# YOTSUBA_GNSS-receiver_MAX_ver_1_5b.net
KiCad netlist of a schematic drawn in EAGLE
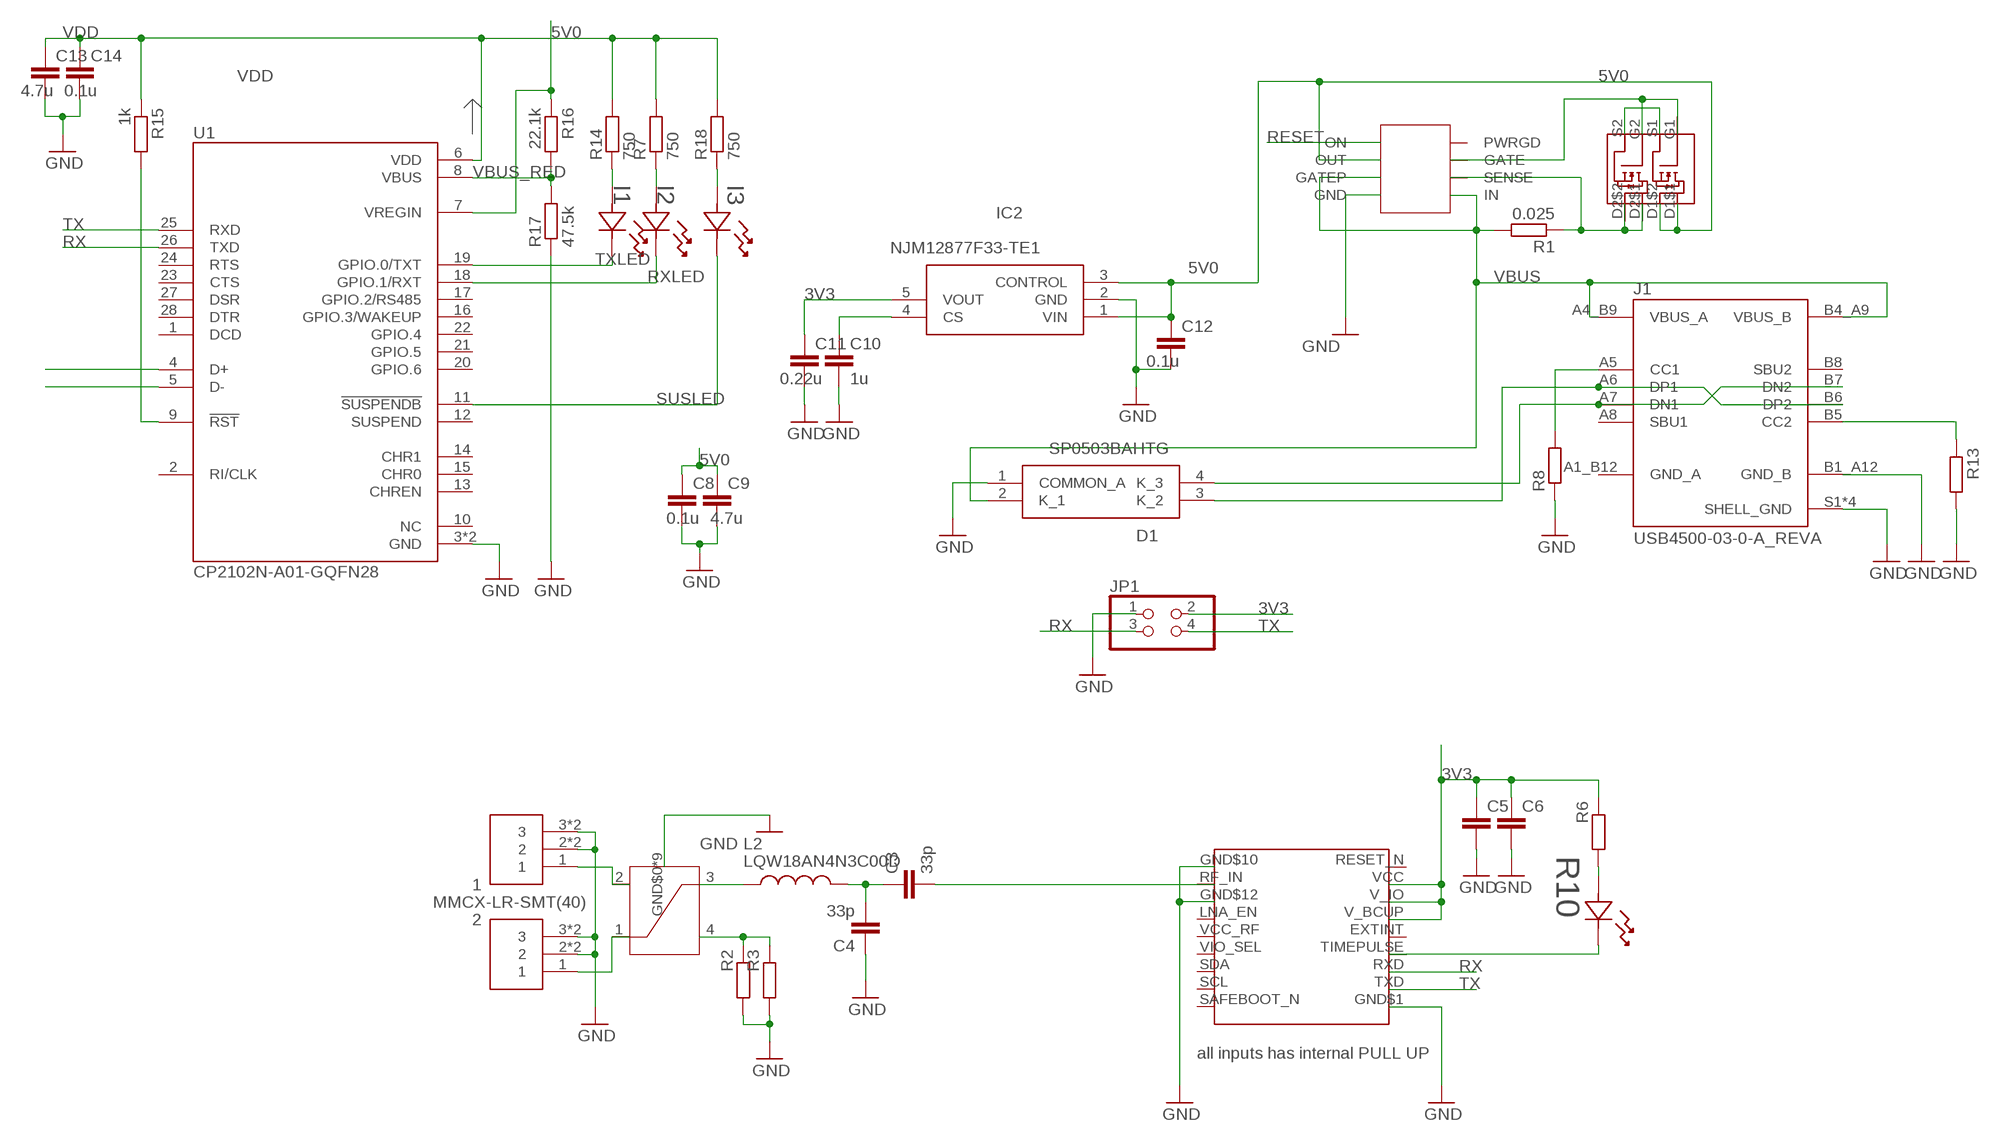
[diagram p0: schematic, sheet 1]

(export (version "E")
  (design (tool "Eeschema 10.0.6"))
  (components
    (comp (ref "1")
      (value "MMCX-LR-SMT(40)")
      (footprint "eagle-import:MMCX-LR-SMT(40)")
      (libsource (lib "eagle-import") (part "MMCX-LR-SMT(40)"))
    )
    (comp (ref "2")
      (value "MMCX-LR-SMT(40)")
      (footprint "eagle-import:MMCX-LR-SMT(40)")
      (libsource (lib "eagle-import") (part "MMCX-LR-SMT(40)"))
    )
    (comp (ref "C3")
      (value "33p")
      (footprint "eagle-import:C1608")
      (libsource (lib "eagle-import") (part "C-EUC1608"))
    )
    (comp (ref "C4")
      (value "33p")
      (footprint "eagle-import:C1608")
      (libsource (lib "eagle-import") (part "C-EUC1608"))
    )
    (comp (ref "C5")
      (value "C-EUC1608")
      (footprint "eagle-import:C1608")
      (libsource (lib "eagle-import") (part "C-EUC1608"))
    )
    (comp (ref "C6")
      (value "C-EUC1608")
      (footprint "eagle-import:C1608")
      (libsource (lib "eagle-import") (part "C-EUC1608"))
    )
    (comp (ref "C8")
      (value "0.1u")
      (footprint "eagle-import:C1608")
      (libsource (lib "eagle-import") (part "C-EUC1608"))
    )
    (comp (ref "C9")
      (value "4.7u")
      (footprint "eagle-import:C1608")
      (libsource (lib "eagle-import") (part "C-EUC1608"))
    )
    (comp (ref "C10")
      (value "1u")
      (footprint "eagle-import:C1608")
      (libsource (lib "eagle-import") (part "C-EUC1608"))
    )
    (comp (ref "C11")
      (value "0.22u")
      (footprint "eagle-import:C1608")
      (libsource (lib "eagle-import") (part "C-EUC1608"))
    )
    (comp (ref "C12")
      (value "0.1u")
      (footprint "eagle-import:C1608")
      (libsource (lib "eagle-import") (part "C-EUC1608"))
    )
    (comp (ref "C13")
      (value "4.7u")
      (footprint "eagle-import:C1608")
      (libsource (lib "eagle-import") (part "C-EUC1608"))
    )
    (comp (ref "C14")
      (value "0.1u")
      (footprint "eagle-import:C1608")
      (libsource (lib "eagle-import") (part "C-EUC1608"))
    )
    (comp (ref "D1")
      (value "SP0503BAHTG")
      (footprint "eagle-import:SP0503BAHTG")
      (fields (field (name "MOUSER_PART_NUMBER") "576-SP0503BAHTG"))
      (libsource (lib "eagle-import") (part "SP0503BAHTG"))
    )
    (comp (ref "I1")
      (value "SML-E12P8WT86")
      (footprint "eagle-import:LED_SMLD12_ROM")
      (fields (field (name "COPYRIGHT") "Copyright (C) 2023 Ultra Librarian. All rights reserved."))
      (libsource (lib "eagle-import") (part "SML-E12P8WT86"))
    )
    (comp (ref "I2")
      (value "SML-E12P8WT86")
      (footprint "eagle-import:LED_SMLD12_ROM")
      (fields (field (name "COPYRIGHT") "Copyright (C) 2023 Ultra Librarian. All rights reserved."))
      (libsource (lib "eagle-import") (part "SML-E12P8WT86"))
    )
    (comp (ref "I3")
      (value "SML-E12P8WT86")
      (footprint "eagle-import:LED_SMLD12_ROM")
      (fields (field (name "COPYRIGHT") "Copyright (C) 2023 Ultra Librarian. All rights reserved."))
      (libsource (lib "eagle-import") (part "SML-E12P8WT86"))
    )
    (comp (ref "IC2")
      (value "NJM12877F33-TE1")
      (footprint "eagle-import:SOT95P280X120-5N")
      (fields (field (name "MOUSER_PART_NUMBER") "513-NJM12877F33-TE1"))
      (libsource (lib "eagle-import") (part "NJM12877F33-TE1"))
    )
    (comp (ref "J1")
      (value "USB4500-03-0-A_REVA")
      (footprint "eagle-import:GCT_USB4500-03-0-A_REVA")
      (fields
        (field (name "DIGI-KEY_PART_NUMBER") "2073-USB4500-03-0-ATR-ND")
        (field (name "MF") "Global Connector Technology")
        (field (name "MP") "USB4500-03-0-A")
      )
      (libsource (lib "eagle-import") (part "USB4500-03-0-A_REVA"))
    )
    (comp (ref "JP1")
      (value "PINHD-2X2")
      (footprint "eagle-import:2X02")
      (libsource (lib "eagle-import") (part "PINHD-2X2"))
    )
    (comp (ref "L2")
      (value "LQW18AN4N3C00D")
      (footprint "eagle-import:INDC1608X100N")
      (fields (field (name "DIGIKEY_PART_NUMBER") "490-6896-2-ND") (field (name "MF") "Murata"))
      (libsource (lib "eagle-import") (part "LQW18AN4N3C00D"))
    )
    (comp (ref "R1")
      (value "0.025")
      (footprint "eagle-import:R0603")
      (libsource (lib "eagle-import") (part "R-EU_R0603"))
    )
    (comp (ref "R2")
      (value "R-EU_R0603")
      (footprint "eagle-import:R0603")
      (libsource (lib "eagle-import") (part "R-EU_R0603"))
    )
    (comp (ref "R3")
      (value "R-EU_R0603")
      (footprint "eagle-import:R0603")
      (libsource (lib "eagle-import") (part "R-EU_R0603"))
    )
    (comp (ref "R6")
      (value "R-EU_R0603")
      (footprint "eagle-import:R0603")
      (libsource (lib "eagle-import") (part "R-EU_R0603"))
    )
    (comp (ref "R7")
      (value "750")
      (footprint "eagle-import:R0603")
      (libsource (lib "eagle-import") (part "R-EU_R0603"))
    )
    (comp (ref "R8")
      (value "R-EU_R0603")
      (footprint "eagle-import:R0603")
      (libsource (lib "eagle-import") (part "R-EU_R0603"))
    )
    (comp (ref "R10")
      (value "SML-E12P8WT86")
      (footprint "eagle-import:LED_SMLD12_ROM")
      (fields (field (name "COPYRIGHT") "Copyright (C) 2023 Ultra Librarian. All rights reserved."))
      (libsource (lib "eagle-import") (part "SML-E12P8WT86"))
    )
    (comp (ref "R13")
      (value "R-EU_R0603")
      (footprint "eagle-import:R0603")
      (libsource (lib "eagle-import") (part "R-EU_R0603"))
    )
    (comp (ref "R14")
      (value "750")
      (footprint "eagle-import:R0603")
      (libsource (lib "eagle-import") (part "R-EU_R0603"))
    )
    (comp (ref "R15")
      (value "1k")
      (footprint "eagle-import:R0603")
      (libsource (lib "eagle-import") (part "R-EU_R0603"))
    )
    (comp (ref "R16")
      (value "22.1k")
      (footprint "eagle-import:R0603")
      (libsource (lib "eagle-import") (part "R-EU_R0603"))
    )
    (comp (ref "R17")
      (value "47.5k")
      (footprint "eagle-import:R0603")
      (libsource (lib "eagle-import") (part "R-EU_R0603"))
    )
    (comp (ref "R18")
      (value "750")
      (footprint "eagle-import:R0603")
      (libsource (lib "eagle-import") (part "R-EU_R0603"))
    )
    (comp (ref "U$1")
      (value "MAX_M10S")
      (footprint "eagle-import:MAX-M10S")
      (libsource (lib "eagle-import") (part "MAX_M10S"))
    )
    (comp (ref "U$3")
      (value "HC125.A")
      (footprint "eagle-import:HC125.A")
      (libsource (lib "eagle-import") (part "HC125.A"))
    )
    (comp (ref "U$7")
      (value "DMG6898LSD")
      (footprint "eagle-import:SOIC127P600X150-8N")
      (libsource (lib "eagle-import") (part "DMG6898LSD"))
    )
    (comp (ref "U$8")
      (value "LTC4361")
      (footprint "eagle-import:SOP65P280X100-8N")
      (libsource (lib "eagle-import") (part "LTC4361"))
    )
    (comp (ref "U1")
      (value "CP2102N-A01-GQFN28")
      (footprint "eagle-import:QFN50P500X500X80-29N")
      (fields (field (name "MF") "Silicon Labs"))
      (libsource (lib "eagle-import") (part "CP2102N-A01-GQFN28"))
    )
  )
  (nets
    (net (code "1") (name "/3V3") (class "Default")
      (node (ref "C11") (pin "1") (pinfunction "1_1") (pintype "passive"))
      (node (ref "C5") (pin "1") (pinfunction "1_1") (pintype "passive"))
      (node (ref "C6") (pin "1") (pinfunction "1_1") (pintype "passive"))
      (node (ref "IC2") (pin "5") (pinfunction "VOUT_5") (pintype "bidirectional"))
      (node (ref "JP1") (pin "2") (pinfunction "2_2") (pintype "passive"))
      (node (ref "R6") (pin "2") (pinfunction "2_2") (pintype "passive"))
      (node (ref "U$1") (pin "VCC") (pinfunction "VCC_VCC") (pintype "bidirectional"))
      (node (ref "U$1") (pin "V_BCUP") (pinfunction "V_BCKP_V_BCUP") (pintype "bidirectional"))
      (node (ref "U$1") (pin "V_IO") (pinfunction "V_IO_V_IO") (pintype "bidirectional"))
    )
    (net (code "2") (name "/5V0") (class "Default")
      (node (ref "C12") (pin "1") (pinfunction "1_1") (pintype "passive"))
      (node (ref "C8") (pin "1") (pinfunction "1_1") (pintype "passive"))
      (node (ref "C9") (pin "1") (pinfunction "1_1") (pintype "passive"))
      (node (ref "IC2") (pin "1") (pinfunction "VIN_1") (pintype "bidirectional"))
      (node (ref "IC2") (pin "3") (pinfunction "CONTROL_3") (pintype "bidirectional"))
      (node (ref "R16") (pin "1") (pinfunction "1_1") (pintype "passive"))
      (node (ref "U$7") (pin "D1$1") (pinfunction "D1$1_D1$1") (pintype "bidirectional"))
      (node (ref "U$7") (pin "D1$2") (pinfunction "D1$2_D1$2") (pintype "bidirectional"))
      (node (ref "U$8") (pin "OUT") (pinfunction "OUT_OUT") (pintype "bidirectional"))
      (node (ref "U1") (pin "7") (pinfunction "VREGIN_7") (pintype "power_in"))
    )
    (net (code "3") (name "/D+") (class "Default")
      (node (ref "D1") (pin "3") (pinfunction "K_2_3") (pintype "bidirectional"))
      (node (ref "J1") (pin "A6") (pinfunction "DP1_A6") (pintype "bidirectional"))
      (node (ref "J1") (pin "B6") (pinfunction "DP2_B6") (pintype "bidirectional"))
      (node (ref "U1") (pin "4") (pinfunction "D+_4") (pintype "bidirectional"))
    )
    (net (code "4") (name "/D-") (class "Default")
      (node (ref "D1") (pin "4") (pinfunction "K_3_4") (pintype "bidirectional"))
      (node (ref "J1") (pin "A7") (pinfunction "DN1_A7") (pintype "bidirectional"))
      (node (ref "J1") (pin "B7") (pinfunction "DN2_B7") (pintype "bidirectional"))
      (node (ref "U1") (pin "5") (pinfunction "D-_5") (pintype "bidirectional"))
    )
    (net (code "5") (name "/GND_A") (class "Default")
      (node (ref "J1") (pin "A1_B12") (pinfunction "GND_A_A1_B12") (pintype "power_in"))
    )
    (net (code "6") (name "/RESET") (class "Default")
      (node (ref "U$8") (pin "ON") (pinfunction "ON_ON") (pintype "bidirectional"))
    )
    (net (code "7") (name "/RX") (class "Default")
      (node (ref "JP1") (pin "3") (pinfunction "3_3") (pintype "passive"))
      (node (ref "U$1") (pin "RXD") (pinfunction "RXD_RXD") (pintype "bidirectional"))
      (node (ref "U1") (pin "26") (pinfunction "TXD_26") (pintype "output"))
    )
    (net (code "8") (name "/RXLED") (class "Default")
      (node (ref "I2") (pin "1") (pinfunction "1_1") (pintype "passive"))
      (node (ref "U1") (pin "18") (pinfunction "GPIO.1/RXT_18") (pintype "bidirectional"))
    )
    (net (code "9") (name "/SUSLED") (class "Default")
      (node (ref "I3") (pin "1") (pinfunction "1_1") (pintype "passive"))
      (node (ref "U1") (pin "11") (pinfunction "~{SUSPENDB}_11") (pintype "output"))
    )
    (net (code "10") (name "/TX") (class "Default")
      (node (ref "JP1") (pin "4") (pinfunction "4_4") (pintype "passive"))
      (node (ref "U$1") (pin "TXD") (pinfunction "TXD_TXD") (pintype "bidirectional"))
      (node (ref "U1") (pin "25") (pinfunction "RXD_25") (pintype "input"))
    )
    (net (code "11") (name "/TXLED") (class "Default")
      (node (ref "I1") (pin "1") (pinfunction "1_1") (pintype "passive"))
      (node (ref "U1") (pin "19") (pinfunction "GPIO.0/TXT_19") (pintype "bidirectional"))
    )
    (net (code "12") (name "/VBUS") (class "Default")
      (node (ref "D1") (pin "2") (pinfunction "K_1_2") (pintype "bidirectional"))
      (node (ref "J1") (pin "A4_B9") (pinfunction "VBUS_A_A4_B9") (pintype "power_in"))
      (node (ref "J1") (pin "B4_A9") (pinfunction "VBUS_B_B4_A9") (pintype "power_in"))
      (node (ref "R1") (pin "2") (pinfunction "2_2") (pintype "passive"))
      (node (ref "U$8") (pin "GATEP") (pinfunction "GATEP_GATEP") (pintype "bidirectional"))
      (node (ref "U$8") (pin "IN") (pinfunction "IN_IN") (pintype "bidirectional"))
    )
    (net (code "13") (name "/VBUS_RED") (class "Default")
      (node (ref "R16") (pin "2") (pinfunction "2_2") (pintype "passive"))
      (node (ref "R17") (pin "2") (pinfunction "2_2") (pintype "passive"))
      (node (ref "U1") (pin "8") (pinfunction "VBUS_8") (pintype "power_in"))
    )
    (net (code "14") (name "/VDD") (class "Default")
      (node (ref "C13") (pin "1") (pinfunction "1_1") (pintype "passive"))
      (node (ref "C14") (pin "1") (pinfunction "1_1") (pintype "passive"))
      (node (ref "R14") (pin "2") (pinfunction "2_2") (pintype "passive"))
      (node (ref "R15") (pin "1") (pinfunction "1_1") (pintype "passive"))
      (node (ref "R18") (pin "2") (pinfunction "2_2") (pintype "passive"))
      (node (ref "R7") (pin "2") (pinfunction "2_2") (pintype "passive"))
      (node (ref "U1") (pin "6") (pinfunction "VDD_6") (pintype "power_in"))
    )
    (net (code "15") (name "GND") (class "Default")
      (node (ref "1") (pin "2") (pinfunction "2_2") (pintype "bidirectional"))
      (node (ref "1") (pin "3") (pinfunction "3_3") (pintype "bidirectional"))
      (node (ref "1") (pin "4") (pinfunction "2_4") (pintype "bidirectional"))
      (node (ref "1") (pin "5") (pinfunction "3_5") (pintype "bidirectional"))
      (node (ref "2") (pin "2") (pinfunction "2_2") (pintype "bidirectional"))
      (node (ref "2") (pin "3") (pinfunction "3_3") (pintype "bidirectional"))
      (node (ref "2") (pin "4") (pinfunction "2_4") (pintype "bidirectional"))
      (node (ref "2") (pin "5") (pinfunction "3_5") (pintype "bidirectional"))
      (node (ref "C10") (pin "2") (pinfunction "2_2") (pintype "passive"))
      (node (ref "C11") (pin "2") (pinfunction "2_2") (pintype "passive"))
      (node (ref "C12") (pin "2") (pinfunction "2_2") (pintype "passive"))
      (node (ref "C13") (pin "2") (pinfunction "2_2") (pintype "passive"))
      (node (ref "C14") (pin "2") (pinfunction "2_2") (pintype "passive"))
      (node (ref "C4") (pin "1") (pinfunction "1_1") (pintype "passive"))
      (node (ref "C5") (pin "2") (pinfunction "2_2") (pintype "passive"))
      (node (ref "C6") (pin "2") (pinfunction "2_2") (pintype "passive"))
      (node (ref "C8") (pin "2") (pinfunction "2_2") (pintype "passive"))
      (node (ref "C9") (pin "2") (pinfunction "2_2") (pintype "passive"))
      (node (ref "D1") (pin "1") (pinfunction "COMMON_A_1") (pintype "bidirectional"))
      (node (ref "IC2") (pin "2") (pinfunction "GND_2") (pintype "bidirectional"))
      (node (ref "J1") (pin "B1_A12") (pinfunction "GND_B_B1_A12") (pintype "power_in"))
      (node (ref "J1") (pin "S1") (pinfunction "SHELL_GND_S1") (pintype "power_in"))
      (node (ref "J1") (pin "S2") (pinfunction "SHELL_GND_S2") (pintype "power_in"))
      (node (ref "J1") (pin "S3") (pinfunction "SHELL_GND_S3") (pintype "power_in"))
      (node (ref "J1") (pin "S4") (pinfunction "SHELL_GND_S4") (pintype "power_in"))
      (node (ref "JP1") (pin "1") (pinfunction "1_1") (pintype "passive"))
      (node (ref "R13") (pin "2") (pinfunction "2_2") (pintype "passive"))
      (node (ref "R17") (pin "1") (pinfunction "1_1") (pintype "passive"))
      (node (ref "R2") (pin "1") (pinfunction "1_1") (pintype "passive"))
      (node (ref "R3") (pin "1") (pinfunction "1_1") (pintype "passive"))
      (node (ref "R8") (pin "1") (pinfunction "1_1") (pintype "passive"))
      (node (ref "U$1") (pin "GND$1") (pinfunction "GND$1_GND$1") (pintype "bidirectional"))
      (node (ref "U$1") (pin "GND$10") (pinfunction "GND$10_GND$10") (pintype "bidirectional"))
      (node (ref "U$1") (pin "GND$12") (pinfunction "GND$12_GND$12") (pintype "bidirectional"))
      (node (ref "U$3") (pin "GND$0") (pinfunction "GND_GND$0") (pintype "bidirectional"))
      (node (ref "U$3") (pin "GND$1") (pinfunction "GND_GND$1") (pintype "bidirectional"))
      (node (ref "U$3") (pin "GND$2") (pinfunction "GND_GND$2") (pintype "bidirectional"))
      (node (ref "U$3") (pin "GND$3") (pinfunction "GND_GND$3") (pintype "bidirectional"))
      (node (ref "U$3") (pin "GND$4") (pinfunction "GND_GND$4") (pintype "bidirectional"))
      (node (ref "U$3") (pin "GND$5") (pinfunction "GND_GND$5") (pintype "bidirectional"))
      (node (ref "U$3") (pin "GND$6") (pinfunction "GND_GND$6") (pintype "bidirectional"))
      (node (ref "U$3") (pin "GND$7") (pinfunction "GND_GND$7") (pintype "bidirectional"))
      (node (ref "U$3") (pin "GND$8") (pinfunction "GND_GND$8") (pintype "bidirectional"))
      (node (ref "U$8") (pin "GND") (pinfunction "GND_GND") (pintype "bidirectional"))
      (node (ref "U1") (pin "29") (pinfunction "GND_29") (pintype "power_in"))
      (node (ref "U1") (pin "3") (pinfunction "GND_3") (pintype "power_in"))
    )
    (net (code "16") (name "Net-(1-Pad1)") (class "Default")
      (node (ref "1") (pin "1") (pinfunction "1_1") (pintype "bidirectional"))
      (node (ref "U$3") (pin "2") (pinfunction "2_2") (pintype "bidirectional"))
    )
    (net (code "17") (name "Net-(2-Pad1)") (class "Default")
      (node (ref "2") (pin "1") (pinfunction "1_1") (pintype "bidirectional"))
      (node (ref "U$3") (pin "1") (pinfunction "1_1") (pintype "bidirectional"))
    )
    (net (code "18") (name "Net-(C3-Pad1)") (class "Default")
      (node (ref "C3") (pin "1") (pinfunction "1_1") (pintype "passive"))
      (node (ref "C4") (pin "2") (pinfunction "2_2") (pintype "passive"))
      (node (ref "L2") (pin "2") (pinfunction "2_2") (pintype "passive"))
    )
    (net (code "19") (name "Net-(C3-Pad2)") (class "Default")
      (node (ref "C3") (pin "2") (pinfunction "2_2") (pintype "passive"))
      (node (ref "U$1") (pin "RF_IN") (pinfunction "RF_IN_RF_IN") (pintype "bidirectional"))
    )
    (net (code "20") (name "Net-(I1-Pad2)") (class "Default")
      (node (ref "I1") (pin "2") (pinfunction "2_2") (pintype "passive"))
      (node (ref "R14") (pin "1") (pinfunction "1_1") (pintype "passive"))
    )
    (net (code "21") (name "Net-(I2-Pad2)") (class "Default")
      (node (ref "I2") (pin "2") (pinfunction "2_2") (pintype "passive"))
      (node (ref "R7") (pin "1") (pinfunction "1_1") (pintype "passive"))
    )
    (net (code "22") (name "Net-(I3-Pad2)") (class "Default")
      (node (ref "I3") (pin "2") (pinfunction "2_2") (pintype "passive"))
      (node (ref "R18") (pin "1") (pinfunction "1_1") (pintype "passive"))
    )
    (net (code "23") (name "Net-(IC2-CS)") (class "Default")
      (node (ref "C10") (pin "1") (pinfunction "1_1") (pintype "passive"))
      (node (ref "IC2") (pin "4") (pinfunction "CS_4") (pintype "bidirectional"))
    )
    (net (code "24") (name "Net-(J1-CC1)") (class "Default")
      (node (ref "J1") (pin "A5") (pinfunction "CC1_A5") (pintype "bidirectional"))
      (node (ref "R8") (pin "2") (pinfunction "2_2") (pintype "passive"))
    )
    (net (code "25") (name "Net-(J1-CC2)") (class "Default")
      (node (ref "J1") (pin "B5") (pinfunction "CC2_B5") (pintype "bidirectional"))
      (node (ref "R13") (pin "1") (pinfunction "1_1") (pintype "passive"))
    )
    (net (code "26") (name "Net-(L2-Pad1)") (class "Default")
      (node (ref "L2") (pin "1") (pinfunction "1_1") (pintype "passive"))
      (node (ref "U$3") (pin "3") (pinfunction "3_3") (pintype "bidirectional"))
    )
    (net (code "27") (name "Net-(R1-Pad1)") (class "Default")
      (node (ref "R1") (pin "1") (pinfunction "1_1") (pintype "passive"))
      (node (ref "U$7") (pin "D2$1") (pinfunction "D2$1_D2$1") (pintype "bidirectional"))
      (node (ref "U$7") (pin "D2$2") (pinfunction "D2$2_D2$2") (pintype "bidirectional"))
      (node (ref "U$8") (pin "SENSE") (pinfunction "SENSE_SENSE") (pintype "bidirectional"))
    )
    (net (code "28") (name "Net-(R2-Pad2)") (class "Default")
      (node (ref "R2") (pin "2") (pinfunction "2_2") (pintype "passive"))
      (node (ref "R3") (pin "2") (pinfunction "2_2") (pintype "passive"))
      (node (ref "U$3") (pin "4") (pinfunction "4_4") (pintype "bidirectional"))
    )
    (net (code "29") (name "Net-(R10-Pad1)") (class "Default")
      (node (ref "R10") (pin "1") (pinfunction "1_1") (pintype "passive"))
      (node (ref "U$1") (pin "TIMEPULSE") (pinfunction "TIMEPULSE_TIMEPULSE") (pintype "bidirectional"))
    )
    (net (code "30") (name "Net-(R10-Pad2)") (class "Default")
      (node (ref "R10") (pin "2") (pinfunction "2_2") (pintype "passive"))
      (node (ref "R6") (pin "1") (pinfunction "1_1") (pintype "passive"))
    )
    (net (code "31") (name "Net-(U$7-PadG1)") (class "Default")
      (node (ref "U$7") (pin "G1") (pinfunction "G1_G1") (pintype "bidirectional"))
      (node (ref "U$7") (pin "G2") (pinfunction "G2_G2") (pintype "bidirectional"))
      (node (ref "U$8") (pin "GATE") (pinfunction "GATE_GATE") (pintype "bidirectional"))
    )
    (net (code "32") (name "Net-(U$7-PadS1)") (class "Default")
      (node (ref "U$7") (pin "S1") (pinfunction "S1_S1") (pintype "bidirectional"))
      (node (ref "U$7") (pin "S2") (pinfunction "S2_S2") (pintype "bidirectional"))
    )
    (net (code "33") (name "Net-(U1-~{RST})") (class "Default")
      (node (ref "R15") (pin "2") (pinfunction "2_2") (pintype "passive"))
      (node (ref "U1") (pin "9") (pinfunction "~{RST}_9") (pintype "input"))
    )
    (net (code "34") (name "unconnected-(J1-SBU1-PadA8)") (class "Default")
      (node (ref "J1") (pin "A8") (pinfunction "SBU1_A8") (pintype "bidirectional"))
    )
    (net (code "35") (name "unconnected-(J1-SBU2-PadB8)") (class "Default")
      (node (ref "J1") (pin "B8") (pinfunction "SBU2_B8") (pintype "bidirectional"))
    )
    (net (code "36") (name "unconnected-(U$1-PadEXTINT)") (class "Default")
      (node (ref "U$1") (pin "EXTINT") (pinfunction "EXTINT_EXTINT") (pintype "bidirectional"))
    )
    (net (code "37") (name "unconnected-(U$1-PadLNA_EN)") (class "Default")
      (node (ref "U$1") (pin "LNA_EN") (pinfunction "LNA_EN_LNA_EN") (pintype "bidirectional"))
    )
    (net (code "38") (name "unconnected-(U$1-PadRESET_N)") (class "Default")
      (node (ref "U$1") (pin "RESET_N") (pinfunction "RESET_N_RESET_N") (pintype "bidirectional"))
    )
    (net (code "39") (name "unconnected-(U$1-PadSAFEBOOT_N)") (class "Default")
      (node (ref "U$1") (pin "SAFEBOOT_N") (pinfunction "SAFEBOOT_N_SAFEBOOT_N") (pintype "bidirectional"))
    )
    (net (code "40") (name "unconnected-(U$1-PadSCL)") (class "Default")
      (node (ref "U$1") (pin "SCL") (pinfunction "SCL_SCL") (pintype "bidirectional"))
    )
    (net (code "41") (name "unconnected-(U$1-PadSDA)") (class "Default")
      (node (ref "U$1") (pin "SDA") (pinfunction "SDA_SDA") (pintype "bidirectional"))
    )
    (net (code "42") (name "unconnected-(U$1-PadVCC_RF)") (class "Default")
      (node (ref "U$1") (pin "VCC_RF") (pinfunction "VCC_RF_VCC_RF") (pintype "bidirectional"))
    )
    (net (code "43") (name "unconnected-(U$1-PadVIO_SEL)") (class "Default")
      (node (ref "U$1") (pin "VIO_SEL") (pinfunction "VIO_SEL_VIO_SEL") (pintype "bidirectional"))
    )
    (net (code "44") (name "unconnected-(U$8-PadPWRGD)") (class "Default")
      (node (ref "U$8") (pin "PWRGD") (pinfunction "PWRGD_PWRGD") (pintype "bidirectional"))
    )
    (net (code "45") (name "unconnected-(U1-CHR0-Pad15)") (class "Default")
      (node (ref "U1") (pin "15") (pinfunction "CHR0_15") (pintype "output"))
    )
    (net (code "46") (name "unconnected-(U1-CHR1-Pad14)") (class "Default")
      (node (ref "U1") (pin "14") (pinfunction "CHR1_14") (pintype "output"))
    )
    (net (code "47") (name "unconnected-(U1-CHREN-Pad13)") (class "Default")
      (node (ref "U1") (pin "13") (pinfunction "CHREN_13") (pintype "output"))
    )
    (net (code "48") (name "unconnected-(U1-CTS-Pad23)") (class "Default")
      (node (ref "U1") (pin "23") (pinfunction "CTS_23") (pintype "input"))
    )
    (net (code "49") (name "unconnected-(U1-DCD-Pad1)") (class "Default")
      (node (ref "U1") (pin "1") (pinfunction "DCD_1") (pintype "input"))
    )
    (net (code "50") (name "unconnected-(U1-DSR-Pad27)") (class "Default")
      (node (ref "U1") (pin "27") (pinfunction "DSR_27") (pintype "input"))
    )
    (net (code "51") (name "unconnected-(U1-DTR-Pad28)") (class "Default")
      (node (ref "U1") (pin "28") (pinfunction "DTR_28") (pintype "output"))
    )
    (net (code "52") (name "unconnected-(U1-GPIO.2{slash}RS485-Pad17)") (class "Default")
      (node (ref "U1") (pin "17") (pinfunction "GPIO.2/RS485_17") (pintype "bidirectional"))
    )
    (net (code "53") (name "unconnected-(U1-GPIO.3{slash}WAKEUP-Pad16)") (class "Default")
      (node (ref "U1") (pin "16") (pinfunction "GPIO.3/WAKEUP_16") (pintype "bidirectional"))
    )
    (net (code "54") (name "unconnected-(U1-GPIO.4-Pad22)") (class "Default")
      (node (ref "U1") (pin "22") (pinfunction "GPIO.4_22") (pintype "bidirectional"))
    )
    (net (code "55") (name "unconnected-(U1-GPIO.5-Pad21)") (class "Default")
      (node (ref "U1") (pin "21") (pinfunction "GPIO.5_21") (pintype "bidirectional"))
    )
    (net (code "56") (name "unconnected-(U1-GPIO.6-Pad20)") (class "Default")
      (node (ref "U1") (pin "20") (pinfunction "GPIO.6_20") (pintype "bidirectional"))
    )
    (net (code "57") (name "unconnected-(U1-NC-Pad10)") (class "Default")
      (node (ref "U1") (pin "10") (pinfunction "NC_10") (pintype "no_connect"))
    )
    (net (code "58") (name "unconnected-(U1-RI{slash}CLK-Pad2)") (class "Default")
      (node (ref "U1") (pin "2") (pinfunction "RI/CLK_2") (pintype "bidirectional"))
    )
    (net (code "59") (name "unconnected-(U1-RTS-Pad24)") (class "Default")
      (node (ref "U1") (pin "24") (pinfunction "RTS_24") (pintype "output"))
    )
    (net (code "60") (name "unconnected-(U1-SUSPEND-Pad12)") (class "Default")
      (node (ref "U1") (pin "12") (pinfunction "SUSPEND_12") (pintype "output"))
    )
  )
)
